# working.net
KiCad netlist of a schematic drawn in EAGLE
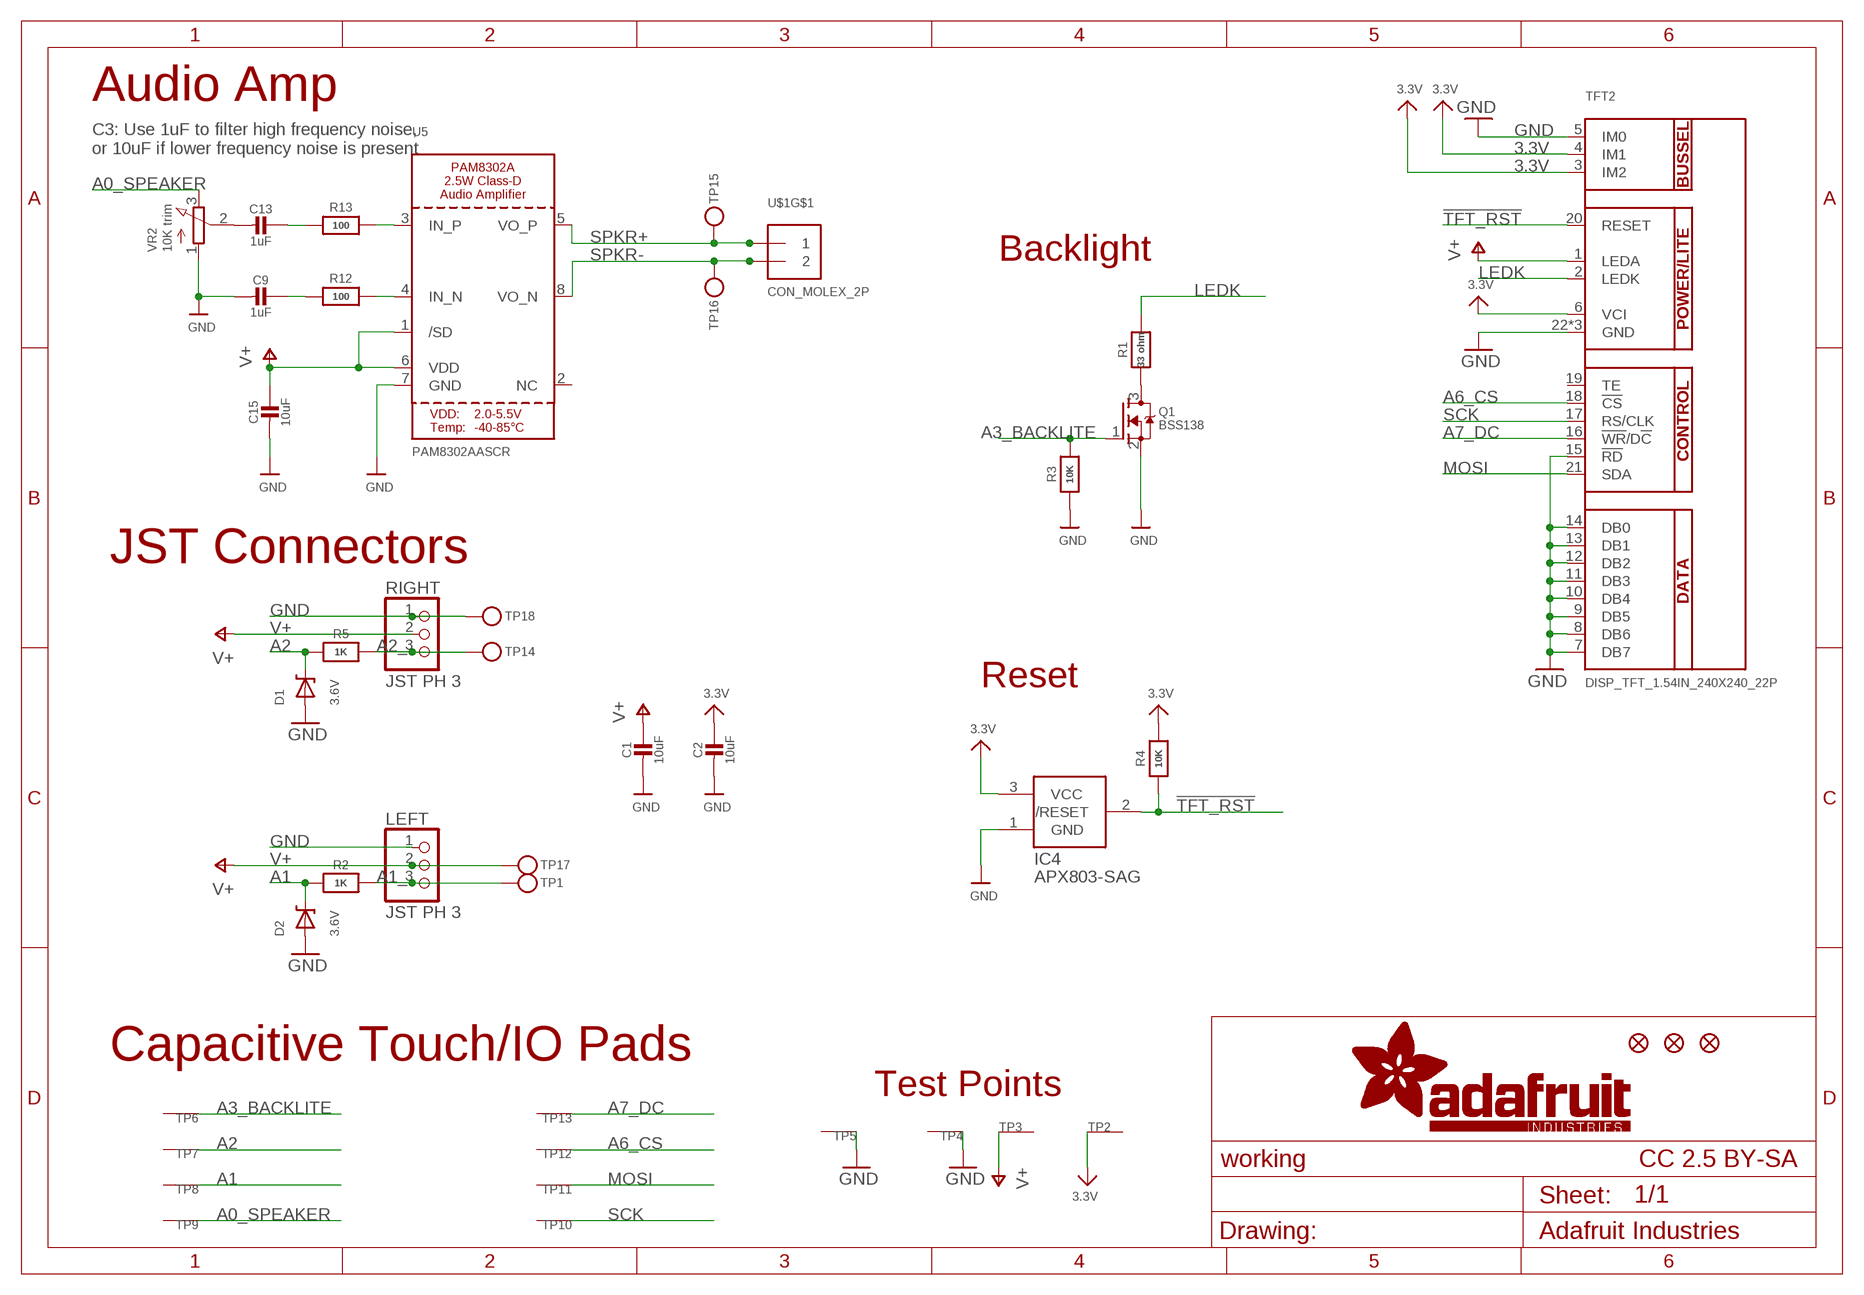
[diagram p0: schematic, sheet 1]

(export (version "E")
  (design (tool "Eeschema 10.0.6"))
  (components
    (comp (ref "C1")
      (value "10uF")
      (footprint "eagle-import:0805-NO")
      (libsource (lib "eagle-import") (part "CAP_CERAMIC0805-NOOUTLINE"))
    )
    (comp (ref "C2")
      (value "10uF")
      (footprint "eagle-import:0805-NO")
      (libsource (lib "eagle-import") (part "CAP_CERAMIC0805-NOOUTLINE"))
    )
    (comp (ref "C9")
      (value "1uF")
      (footprint "eagle-import:0603-NO")
      (libsource (lib "eagle-import") (part "CAP_CERAMIC0603_NO"))
    )
    (comp (ref "C13")
      (value "1uF")
      (footprint "eagle-import:0603-NO")
      (libsource (lib "eagle-import") (part "CAP_CERAMIC0603_NO"))
    )
    (comp (ref "C15")
      (value "10uF")
      (footprint "eagle-import:0805-NO")
      (libsource (lib "eagle-import") (part "CAP_CERAMIC0805-NOOUTLINE"))
    )
    (comp (ref "D1")
      (value "3.6V")
      (footprint "eagle-import:SOD-323")
      (libsource (lib "eagle-import") (part "DIODE-ZENERSOD323"))
    )
    (comp (ref "D2")
      (value "3.6V")
      (footprint "eagle-import:SOD-323")
      (libsource (lib "eagle-import") (part "DIODE-ZENERSOD323"))
    )
    (comp (ref "IC4")
      (value "APX803-SAG")
      (footprint "eagle-import:SOT23")
      (libsource (lib "eagle-import") (part "AXP083-SAG"))
    )
    (comp (ref "LEFT")
      (value "JST PH 3")
      (footprint "eagle-import:JSTPH3")
      (libsource (lib "eagle-import") (part "CON_JST_PH_3PIN"))
    )
    (comp (ref "Q1")
      (value "BSS138")
      (footprint "eagle-import:SOT23-WIDE")
      (libsource (lib "eagle-import") (part "MOSFET-NWIDE"))
    )
    (comp (ref "R1")
      (value "33 ohm")
      (footprint "eagle-import:0603-NO")
      (libsource (lib "eagle-import") (part "RESISTOR_0603_NOOUT"))
    )
    (comp (ref "R2")
      (value "1K")
      (footprint "eagle-import:0603-NO")
      (libsource (lib "eagle-import") (part "RESISTOR_0603_NOOUT"))
    )
    (comp (ref "R3")
      (value "10K")
      (footprint "eagle-import:0603-NO")
      (libsource (lib "eagle-import") (part "RESISTOR_0603_NOOUT"))
    )
    (comp (ref "R4")
      (value "10K")
      (footprint "eagle-import:0603-NO")
      (libsource (lib "eagle-import") (part "RESISTOR_0603_NOOUT"))
    )
    (comp (ref "R5")
      (value "1K")
      (footprint "eagle-import:0603-NO")
      (libsource (lib "eagle-import") (part "RESISTOR_0603_NOOUT"))
    )
    (comp (ref "R12")
      (value "100")
      (footprint "eagle-import:0603-NO")
      (libsource (lib "eagle-import") (part "RESISTOR_0603_NOOUT"))
    )
    (comp (ref "R13")
      (value "100")
      (footprint "eagle-import:0603-NO")
      (libsource (lib "eagle-import") (part "RESISTOR_0603_NOOUT"))
    )
    (comp (ref "RIGHT")
      (value "JST PH 3")
      (footprint "eagle-import:JSTPH3")
      (libsource (lib "eagle-import") (part "CON_JST_PH_3PIN"))
    )
    (comp (ref "TFT2")
      (value "DISP_TFT_1.54IN_240X240_22P")
      (footprint "eagle-import:TFT_1.54IN_240X240_22PIN")
      (libsource (lib "eagle-import") (part "DISP_TFT_1.54IN_240X240_22P"))
    )
    (comp (ref "TP1")
      (value "TESTPOINTROUND1.5MMNO")
      (footprint "eagle-import:TESTPOINT_ROUND_1.5MM_NO")
      (libsource (lib "eagle-import") (part "TESTPOINTROUND1.5MMNO"))
    )
    (comp (ref "TP2")
      (value "SEWTAP_SMTNUTM3")
      (footprint "eagle-import:SMT_NUT_3MM")
      (libsource (lib "eagle-import") (part "SEWTAP_SMTNUTM3"))
    )
    (comp (ref "TP3")
      (value "SEWTAP_SMTNUTM3")
      (footprint "eagle-import:SMT_NUT_3MM")
      (libsource (lib "eagle-import") (part "SEWTAP_SMTNUTM3"))
    )
    (comp (ref "TP4")
      (value "SEWTAP_SMTNUTM3")
      (footprint "eagle-import:SMT_NUT_3MM")
      (libsource (lib "eagle-import") (part "SEWTAP_SMTNUTM3"))
    )
    (comp (ref "TP5")
      (value "SEWTAP_SMTNUTM3")
      (footprint "eagle-import:SMT_NUT_3MM")
      (libsource (lib "eagle-import") (part "SEWTAP_SMTNUTM3"))
    )
    (comp (ref "TP6")
      (value "SEWTAP_SMTNUTM3")
      (footprint "eagle-import:SMT_NUT_3MM")
      (libsource (lib "eagle-import") (part "SEWTAP_SMTNUTM3"))
    )
    (comp (ref "TP7")
      (value "SEWTAP_SMTNUTM3")
      (footprint "eagle-import:SMT_NUT_3MM")
      (libsource (lib "eagle-import") (part "SEWTAP_SMTNUTM3"))
    )
    (comp (ref "TP8")
      (value "SEWTAP_SMTNUTM3")
      (footprint "eagle-import:SMT_NUT_3MM")
      (libsource (lib "eagle-import") (part "SEWTAP_SMTNUTM3"))
    )
    (comp (ref "TP9")
      (value "SEWTAP_SMTNUTM3")
      (footprint "eagle-import:SMT_NUT_3MM")
      (libsource (lib "eagle-import") (part "SEWTAP_SMTNUTM3"))
    )
    (comp (ref "TP10")
      (value "SEWTAP_SMTNUTM3")
      (footprint "eagle-import:SMT_NUT_3MM")
      (libsource (lib "eagle-import") (part "SEWTAP_SMTNUTM3"))
    )
    (comp (ref "TP11")
      (value "SEWTAP_SMTNUTM3")
      (footprint "eagle-import:SMT_NUT_3MM")
      (libsource (lib "eagle-import") (part "SEWTAP_SMTNUTM3"))
    )
    (comp (ref "TP12")
      (value "SEWTAP_SMTNUTM3")
      (footprint "eagle-import:SMT_NUT_3MM")
      (libsource (lib "eagle-import") (part "SEWTAP_SMTNUTM3"))
    )
    (comp (ref "TP13")
      (value "SEWTAP_SMTNUTM3")
      (footprint "eagle-import:SMT_NUT_3MM")
      (libsource (lib "eagle-import") (part "SEWTAP_SMTNUTM3"))
    )
    (comp (ref "TP14")
      (value "TESTPOINTROUND1.5MMNO")
      (footprint "eagle-import:TESTPOINT_ROUND_1.5MM_NO")
      (libsource (lib "eagle-import") (part "TESTPOINTROUND1.5MMNO"))
    )
    (comp (ref "TP15")
      (value "TESTPOINTROUND1.5MMNO")
      (footprint "eagle-import:TESTPOINT_ROUND_1.5MM_NO")
      (libsource (lib "eagle-import") (part "TESTPOINTROUND1.5MMNO"))
    )
    (comp (ref "TP16")
      (value "TESTPOINTROUND1.5MMNO")
      (footprint "eagle-import:TESTPOINT_ROUND_1.5MM_NO")
      (libsource (lib "eagle-import") (part "TESTPOINTROUND1.5MMNO"))
    )
    (comp (ref "TP17")
      (value "TESTPOINTROUND1.5MMNO")
      (footprint "eagle-import:TESTPOINT_ROUND_1.5MM_NO")
      (libsource (lib "eagle-import") (part "TESTPOINTROUND1.5MMNO"))
    )
    (comp (ref "TP18")
      (value "TESTPOINTROUND1.5MMNO")
      (footprint "eagle-import:TESTPOINT_ROUND_1.5MM_NO")
      (libsource (lib "eagle-import") (part "TESTPOINTROUND1.5MMNO"))
    )
    (comp (ref "U$1")
      (value "CON_MOLEX_2P")
      (footprint "eagle-import:53398-0271")
      (libsource (lib "eagle-import") (part "CON_MOLEX_2P"))
    )
    (comp (ref "U$2")
      (value "FIDUCIAL_1MM")
      (footprint "eagle-import:FIDUCIAL_1MM")
      (libsource (lib "eagle-import") (part "FIDUCIAL_1MM"))
    )
    (comp (ref "U$3")
      (value "FIDUCIAL_1MM")
      (footprint "eagle-import:FIDUCIAL_1MM")
      (fields (field (name "BOM") "EXCLUDE"))
      (libsource (lib "eagle-import") (part "FIDUCIAL_1MM"))
    )
    (comp (ref "U$6")
      (value "FIDUCIAL_1MM")
      (footprint "eagle-import:FIDUCIAL_1MM")
      (libsource (lib "eagle-import") (part "FIDUCIAL_1MM"))
    )
    (comp (ref "U5")
      (value "PAM8302AASCR")
      (footprint "eagle-import:MSOP8_0.65MM")
      (libsource (lib "eagle-import") (part "AUDIOAMP_PAM8302A"))
    )
    (comp (ref "VR2")
      (value "10K trim")
      (footprint "eagle-import:TRIMPOT_BOURNS_3303W")
      (libsource (lib "eagle-import") (part "TRIMPOT3303W/X"))
    )
  )
  (nets
    (net (code "1") (name "/A0_SPEAKER") (class "Default")
      (node (ref "TP9") (pin "P$1") (pinfunction "SEW_P$1") (pintype "bidirectional"))
      (node (ref "VR2") (pin "3") (pinfunction "E_3") (pintype "passive"))
    )
    (net (code "2") (name "/A1") (class "Default")
      (node (ref "D2") (pin "C") (pinfunction "C_C") (pintype "passive"))
      (node (ref "R2") (pin "2") (pinfunction "2_2") (pintype "passive"))
      (node (ref "TP8") (pin "P$1") (pinfunction "SEW_P$1") (pintype "bidirectional"))
    )
    (net (code "3") (name "/A1_") (class "Default")
      (node (ref "LEFT") (pin "3") (pinfunction "3_3") (pintype "passive"))
      (node (ref "R2") (pin "1") (pinfunction "1_1") (pintype "passive"))
      (node (ref "TP1") (pin "P$1") (pinfunction "P$1_P$1") (pintype "bidirectional"))
    )
    (net (code "4") (name "/A2") (class "Default")
      (node (ref "D1") (pin "C") (pinfunction "C_C") (pintype "passive"))
      (node (ref "R5") (pin "2") (pinfunction "2_2") (pintype "passive"))
      (node (ref "TP7") (pin "P$1") (pinfunction "SEW_P$1") (pintype "bidirectional"))
    )
    (net (code "5") (name "/A2_") (class "Default")
      (node (ref "R5") (pin "1") (pinfunction "1_1") (pintype "passive"))
      (node (ref "RIGHT") (pin "3") (pinfunction "3_3") (pintype "passive"))
      (node (ref "TP14") (pin "P$1") (pinfunction "P$1_P$1") (pintype "bidirectional"))
    )
    (net (code "6") (name "/A3_BACKLITE") (class "Default")
      (node (ref "Q1") (pin "1") (pinfunction "G_1") (pintype "bidirectional"))
      (node (ref "R3") (pin "2") (pinfunction "2_2") (pintype "passive"))
      (node (ref "TP6") (pin "P$1") (pinfunction "SEW_P$1") (pintype "bidirectional"))
    )
    (net (code "7") (name "/A6_CS") (class "Default")
      (node (ref "TFT2") (pin "18") (pinfunction "~{CS}_18") (pintype "input"))
      (node (ref "TP12") (pin "P$1") (pinfunction "SEW_P$1") (pintype "bidirectional"))
    )
    (net (code "8") (name "/A7_DC") (class "Default")
      (node (ref "TFT2") (pin "16") (pinfunction "~{WR}/D~{C}_16") (pintype "input"))
      (node (ref "TP13") (pin "P$1") (pinfunction "SEW_P$1") (pintype "bidirectional"))
    )
    (net (code "9") (name "/LEDK") (class "Default")
      (node (ref "R1") (pin "2") (pinfunction "2_2") (pintype "passive"))
      (node (ref "TFT2") (pin "2") (pinfunction "LEDK_2") (pintype "input"))
    )
    (net (code "10") (name "/MOSI") (class "Default")
      (node (ref "TFT2") (pin "21") (pinfunction "SDA_21") (pintype "bidirectional"))
      (node (ref "TP11") (pin "P$1") (pinfunction "SEW_P$1") (pintype "bidirectional"))
    )
    (net (code "11") (name "/SCK") (class "Default")
      (node (ref "TFT2") (pin "17") (pinfunction "RS/CLK_17") (pintype "input"))
      (node (ref "TP10") (pin "P$1") (pinfunction "SEW_P$1") (pintype "bidirectional"))
    )
    (net (code "12") (name "/SPKR+") (class "Default")
      (node (ref "TP15") (pin "P$1") (pinfunction "P$1_P$1") (pintype "bidirectional"))
      (node (ref "U$1") (pin "1") (pinfunction "1_1") (pintype "passive"))
      (node (ref "U5") (pin "5") (pinfunction "VO_P_5") (pintype "output"))
    )
    (net (code "13") (name "/SPKR-") (class "Default")
      (node (ref "TP16") (pin "P$1") (pinfunction "P$1_P$1") (pintype "bidirectional"))
      (node (ref "U$1") (pin "2") (pinfunction "2_2") (pintype "passive"))
      (node (ref "U5") (pin "8") (pinfunction "VO_N_8") (pintype "output"))
    )
    (net (code "14") (name "/~{TFT_RST}") (class "Default")
      (node (ref "IC4") (pin "2") (pinfunction "/RESET_2") (pintype "output"))
      (node (ref "R4") (pin "1") (pinfunction "1_1") (pintype "passive"))
      (node (ref "TFT2") (pin "20") (pinfunction "RESET_20") (pintype "input"))
    )
    (net (code "15") (name "3.3V") (class "Default")
      (node (ref "C2") (pin "1") (pinfunction "1_1") (pintype "passive"))
      (node (ref "IC4") (pin "3") (pinfunction "VCC_3") (pintype "power_in"))
      (node (ref "R4") (pin "2") (pinfunction "2_2") (pintype "passive"))
      (node (ref "TFT2") (pin "3") (pinfunction "IM2_3") (pintype "input"))
      (node (ref "TFT2") (pin "4") (pinfunction "IM1_4") (pintype "input"))
      (node (ref "TFT2") (pin "6") (pinfunction "VCI_6") (pintype "power_in"))
      (node (ref "TP2") (pin "P$1") (pinfunction "SEW_P$1") (pintype "bidirectional"))
    )
    (net (code "16") (name "GND") (class "Default")
      (node (ref "C1") (pin "2") (pinfunction "2_2") (pintype "passive"))
      (node (ref "C15") (pin "2") (pinfunction "2_2") (pintype "passive"))
      (node (ref "C2") (pin "2") (pinfunction "2_2") (pintype "passive"))
      (node (ref "C9") (pin "2") (pinfunction "2_2") (pintype "passive"))
      (node (ref "D1") (pin "A") (pinfunction "A_A") (pintype "passive"))
      (node (ref "D2") (pin "A") (pinfunction "A_A") (pintype "passive"))
      (node (ref "IC4") (pin "1") (pinfunction "GND_1") (pintype "power_in"))
      (node (ref "LEFT") (pin "1") (pinfunction "1_1") (pintype "passive"))
      (node (ref "Q1") (pin "2") (pinfunction "S_2") (pintype "bidirectional"))
      (node (ref "R3") (pin "1") (pinfunction "1_1") (pintype "passive"))
      (node (ref "RIGHT") (pin "1") (pinfunction "1_1") (pintype "passive"))
      (node (ref "TFT2") (pin "10") (pinfunction "DB4_10") (pintype "bidirectional"))
      (node (ref "TFT2") (pin "11") (pinfunction "DB3_11") (pintype "bidirectional"))
      (node (ref "TFT2") (pin "12") (pinfunction "DB2_12") (pintype "bidirectional"))
      (node (ref "TFT2") (pin "13") (pinfunction "DB1_13") (pintype "bidirectional"))
      (node (ref "TFT2") (pin "14") (pinfunction "DB0_14") (pintype "bidirectional"))
      (node (ref "TFT2") (pin "15") (pinfunction "~{RD}_15") (pintype "input"))
      (node (ref "TFT2") (pin "22") (pinfunction "GND_22") (pintype "power_in"))
      (node (ref "TFT2") (pin "5") (pinfunction "IM0_5") (pintype "input"))
      (node (ref "TFT2") (pin "7") (pinfunction "DB7_7") (pintype "bidirectional"))
      (node (ref "TFT2") (pin "8") (pinfunction "DB6_8") (pintype "bidirectional"))
      (node (ref "TFT2") (pin "9") (pinfunction "DB5_9") (pintype "bidirectional"))
      (node (ref "TFT2") (pin "SUPPORT1") (pinfunction "GND_SUPPORT1") (pintype "power_in"))
      (node (ref "TFT2") (pin "SUPPORT2") (pinfunction "GND_SUPPORT2") (pintype "power_in"))
      (node (ref "TP18") (pin "P$1") (pinfunction "P$1_P$1") (pintype "bidirectional"))
      (node (ref "TP4") (pin "P$1") (pinfunction "SEW_P$1") (pintype "bidirectional"))
      (node (ref "TP5") (pin "P$1") (pinfunction "SEW_P$1") (pintype "bidirectional"))
      (node (ref "U5") (pin "7") (pinfunction "GND_7") (pintype "power_in"))
      (node (ref "VR2") (pin "1") (pinfunction "A_1") (pintype "passive"))
    )
    (net (code "17") (name "Net-(C9-Pad1)") (class "Default")
      (node (ref "C9") (pin "1") (pinfunction "1_1") (pintype "passive"))
      (node (ref "R12") (pin "1") (pinfunction "1_1") (pintype "passive"))
    )
    (net (code "18") (name "Net-(C13-Pad1)") (class "Default")
      (node (ref "C13") (pin "1") (pinfunction "1_1") (pintype "passive"))
      (node (ref "R13") (pin "1") (pinfunction "1_1") (pintype "passive"))
    )
    (net (code "19") (name "Net-(Q1-D)") (class "Default")
      (node (ref "Q1") (pin "3") (pinfunction "D_3") (pintype "bidirectional"))
      (node (ref "R1") (pin "1") (pinfunction "1_1") (pintype "passive"))
    )
    (net (code "20") (name "Net-(U5-IN_N)") (class "Default")
      (node (ref "R12") (pin "2") (pinfunction "2_2") (pintype "passive"))
      (node (ref "U5") (pin "4") (pinfunction "IN_N_4") (pintype "input"))
    )
    (net (code "21") (name "Net-(U5-IN_P)") (class "Default")
      (node (ref "R13") (pin "2") (pinfunction "2_2") (pintype "passive"))
      (node (ref "U5") (pin "3") (pinfunction "IN_P_3") (pintype "input"))
    )
    (net (code "22") (name "Net-(VR2-S)") (class "Default")
      (node (ref "C13") (pin "2") (pinfunction "2_2") (pintype "passive"))
      (node (ref "VR2") (pin "2") (pinfunction "S_2") (pintype "passive"))
    )
    (net (code "23") (name "V+") (class "Default")
      (node (ref "C1") (pin "1") (pinfunction "1_1") (pintype "passive"))
      (node (ref "C15") (pin "1") (pinfunction "1_1") (pintype "passive"))
      (node (ref "LEFT") (pin "2") (pinfunction "2_2") (pintype "passive"))
      (node (ref "RIGHT") (pin "2") (pinfunction "2_2") (pintype "passive"))
      (node (ref "TFT2") (pin "1") (pinfunction "LEDA_1") (pintype "input"))
      (node (ref "TP17") (pin "P$1") (pinfunction "P$1_P$1") (pintype "bidirectional"))
      (node (ref "TP3") (pin "P$1") (pinfunction "SEW_P$1") (pintype "bidirectional"))
      (node (ref "U5") (pin "1") (pinfunction "/SD_1") (pintype "input"))
      (node (ref "U5") (pin "6") (pinfunction "VDD_6") (pintype "power_in"))
    )
    (net (code "24") (name "unconnected-(TFT2-TE-Pad19)") (class "Default")
      (node (ref "TFT2") (pin "19") (pinfunction "TE_19") (pintype "output"))
    )
    (net (code "25") (name "unconnected-(U5-NC-Pad2)") (class "Default")
      (node (ref "U5") (pin "2") (pinfunction "NC_2") (pintype "no_connect"))
    )
  )
)
